# Electric_Scheme.net
KiCad netlist of a schematic drawn in EAGLE
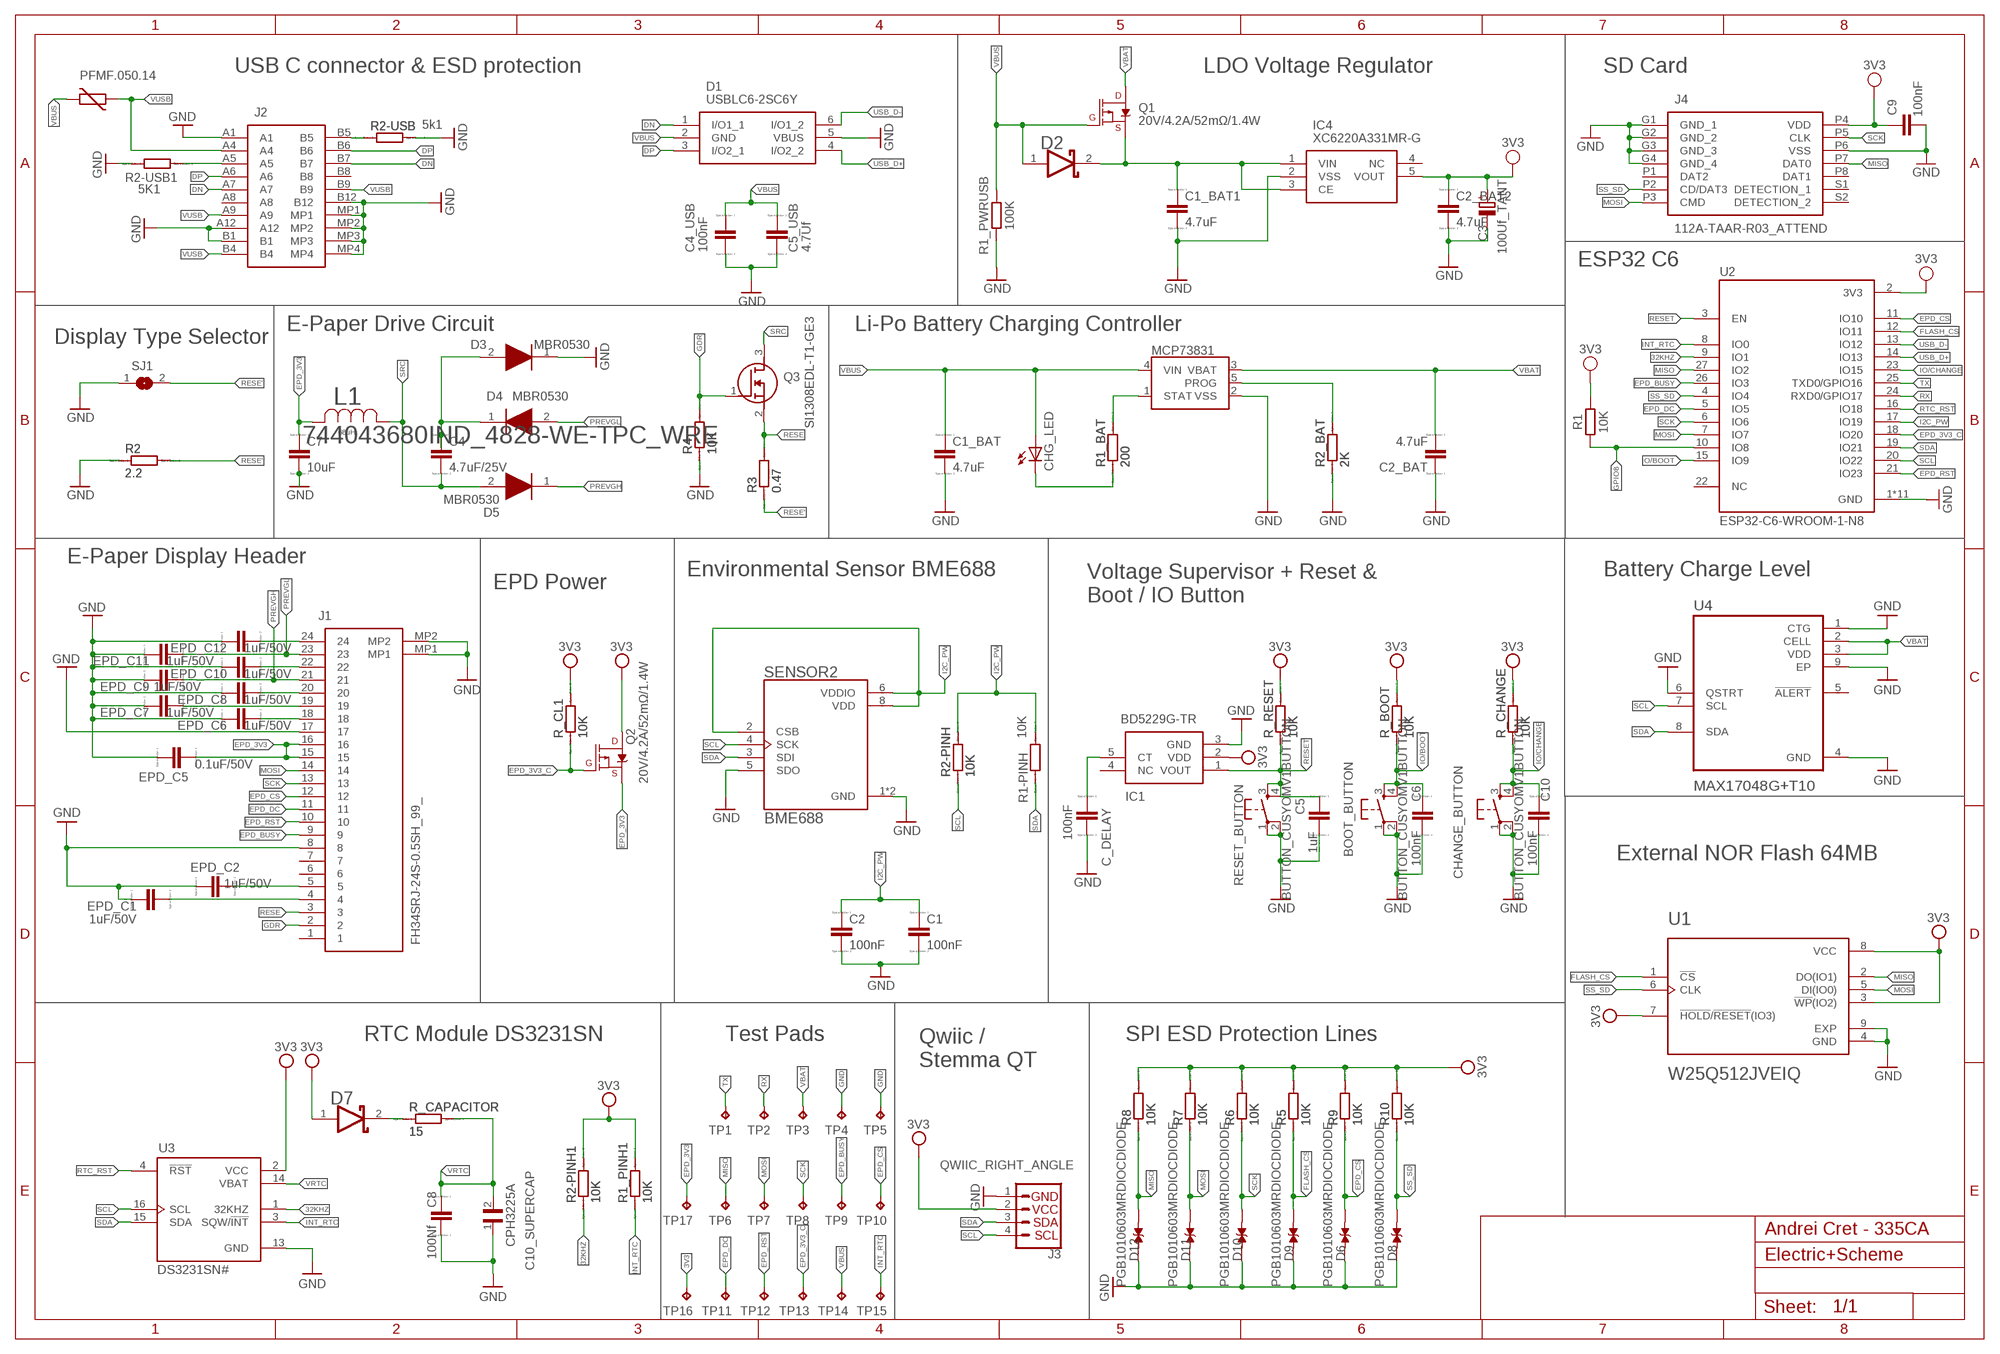
[diagram p0: schematic, sheet 1]

(export (version "E")
  (design (tool "Eeschema 10.0.6"))
  (components
    (comp (ref "BOOT_BUTTON")
      (value "BUTTON_CUSYOMV1BUTTON")
      (footprint "eagle-import:MYBUTTON")
      (libsource (lib "eagle-import") (part "BUTTON_CUSYOMV1BUTTON"))
    )
    (comp (ref "C1")
      (value "100nF")
      (footprint "eagle-import:EAGLE-LTSPICE_C0402")
      (libsource (lib "eagle-import") (part "EAGLE-LTSPICE_C"))
    )
    (comp (ref "C1_BAT")
      (value "4.7uF")
      (footprint "eagle-import:EAGLE-LTSPICE_C0402")
      (libsource (lib "eagle-import") (part "EAGLE-LTSPICE_C"))
    )
    (comp (ref "C1_BAT1")
      (value "4.7uF")
      (footprint "eagle-import:EAGLE-LTSPICE_C0402")
      (libsource (lib "eagle-import") (part "EAGLE-LTSPICE_C"))
    )
    (comp (ref "C2")
      (value "100nF")
      (footprint "eagle-import:EAGLE-LTSPICE_C0402")
      (libsource (lib "eagle-import") (part "EAGLE-LTSPICE_C"))
    )
    (comp (ref "C2_BAT")
      (value "4.7uF")
      (footprint "eagle-import:EAGLE-LTSPICE_C0402")
      (libsource (lib "eagle-import") (part "EAGLE-LTSPICE_C"))
    )
    (comp (ref "C2_BAT2")
      (value "4.7uF")
      (footprint "eagle-import:EAGLE-LTSPICE_C0402")
      (libsource (lib "eagle-import") (part "EAGLE-LTSPICE_C"))
    )
    (comp (ref "C3")
      (value "100Uf_TANT")
      (footprint "eagle-import:CAPMP3216X180N")
      (libsource (lib "eagle-import") (part "CAPACITOR-POLTANTALUM-1206(3216-METRIC)_"))
    )
    (comp (ref "C4")
      (value "4.7uF/25V")
      (footprint "eagle-import:EAGLE-LTSPICE_C0402")
      (libsource (lib "eagle-import") (part "EAGLE-LTSPICE_C"))
    )
    (comp (ref "C4_USB")
      (value "100nF")
      (footprint "eagle-import:EAGLE-LTSPICE_C0402")
      (libsource (lib "eagle-import") (part "EAGLE-LTSPICE_C"))
    )
    (comp (ref "C5")
      (value "1uF")
      (footprint "eagle-import:EAGLE-LTSPICE_C0402")
      (libsource (lib "eagle-import") (part "EAGLE-LTSPICE_C"))
    )
    (comp (ref "C5_USB")
      (value "4.7Uf")
      (footprint "eagle-import:EAGLE-LTSPICE_C0402")
      (libsource (lib "eagle-import") (part "EAGLE-LTSPICE_C"))
    )
    (comp (ref "C6")
      (value "100nF")
      (footprint "eagle-import:EAGLE-LTSPICE_C0402")
      (libsource (lib "eagle-import") (part "EAGLE-LTSPICE_C"))
    )
    (comp (ref "C7")
      (value "10uF")
      (footprint "eagle-import:EAGLE-LTSPICE_C0402")
      (libsource (lib "eagle-import") (part "EAGLE-LTSPICE_C"))
    )
    (comp (ref "C8")
      (value "100Nf")
      (footprint "eagle-import:ESP32_WROVER_EAGLE-LTSPICE_C0402")
      (libsource (lib "eagle-import") (part "ESP32_WROVER_EAGLE-LTSPICE_C"))
    )
    (comp (ref "C9")
      (value "100nF")
      (footprint "eagle-import:CAPC1005X60")
      (libsource (lib "eagle-import") (part "CAPACITORCHIP-0402(1005-METRIC)_"))
    )
    (comp (ref "C10")
      (value "100nF")
      (footprint "eagle-import:EAGLE-LTSPICE_C0402")
      (libsource (lib "eagle-import") (part "EAGLE-LTSPICE_C"))
    )
    (comp (ref "C10_SUPERCAP")
      (value "CPH3225A")
      (footprint "eagle-import:CAPCP3225X100N")
      (fields (field (name "MF") "Seiko Instruments"))
      (libsource (lib "eagle-import") (part "CPH3225A"))
    )
    (comp (ref "CHANGE_BUTTON")
      (value "BUTTON_CUSYOMV1BUTTON")
      (footprint "eagle-import:MYBUTTON")
      (libsource (lib "eagle-import") (part "BUTTON_CUSYOMV1BUTTON"))
    )
    (comp (ref "CHG_LED")
      (value "RED")
      (footprint "eagle-import:ADAFRUIT_CHIP-LED0603")
      (libsource (lib "eagle-import") (part "ADAFRUIT_LEDCHIP-LED0603"))
    )
    (comp (ref "C_DELAY")
      (value "100nF")
      (footprint "eagle-import:EAGLE-LTSPICE_C0402")
      (libsource (lib "eagle-import") (part "EAGLE-LTSPICE_C"))
    )
    (comp (ref "D1")
      (value "USBLC6-2SC6Y")
      (footprint "eagle-import:SOT95P280X145-6N")
      (fields (field (name "MF") "STMicroelectronics"))
      (libsource (lib "eagle-import") (part "USBLC6-2SC6Y"))
    )
    (comp (ref "D2")
      (value "ESP32_WROVER_AVX---SD0805S020S1R0_AVX_SD0805S020S1R0_0_0")
      (footprint "eagle-import:ESP32_WROVER_AVX---SD0805S020S1R0_AVX_SD0805S020S1R0_0")
      (libsource (lib "eagle-import") (part "ESP32_WROVER_AVX---SD0805S020S1R0_AVX_SD0805S020S1R0_0_0"))
    )
    (comp (ref "D3")
      (value "MBR0530")
      (footprint "eagle-import:SOD3716X135N")
      (libsource (lib "eagle-import") (part "MBR0530"))
    )
    (comp (ref "D4")
      (value "MBR0530")
      (footprint "eagle-import:SOD3716X135N")
      (libsource (lib "eagle-import") (part "MBR0530"))
    )
    (comp (ref "D5")
      (value "MBR0530")
      (footprint "eagle-import:SOD3716X135N")
      (libsource (lib "eagle-import") (part "MBR0530"))
    )
    (comp (ref "D6")
      (value "PGB1010603MRDIOCDIODE")
      (footprint "eagle-import:DIOC1608X36N")
      (libsource (lib "eagle-import") (part "PGB1010603MRDIOCDIODE"))
    )
    (comp (ref "D7")
      (value "ESP32_WROVER_AVX---SD0805S020S1R0_AVX_SD0805S020S1R0_0_0")
      (footprint "eagle-import:ESP32_WROVER_AVX---SD0805S020S1R0_AVX_SD0805S020S1R0_0")
      (libsource (lib "eagle-import") (part "ESP32_WROVER_AVX---SD0805S020S1R0_AVX_SD0805S020S1R0_0_0"))
    )
    (comp (ref "D8")
      (value "PGB1010603MRDIOCDIODE")
      (footprint "eagle-import:DIOC1608X36N")
      (libsource (lib "eagle-import") (part "PGB1010603MRDIOCDIODE"))
    )
    (comp (ref "D9")
      (value "PGB1010603MRDIOCDIODE")
      (footprint "eagle-import:DIOC1608X36N")
      (libsource (lib "eagle-import") (part "PGB1010603MRDIOCDIODE"))
    )
    (comp (ref "D10")
      (value "PGB1010603MRDIOCDIODE")
      (footprint "eagle-import:DIOC1608X36N")
      (libsource (lib "eagle-import") (part "PGB1010603MRDIOCDIODE"))
    )
    (comp (ref "D11")
      (value "PGB1010603MRDIOCDIODE")
      (footprint "eagle-import:DIOC1608X36N")
      (libsource (lib "eagle-import") (part "PGB1010603MRDIOCDIODE"))
    )
    (comp (ref "D12")
      (value "PGB1010603MRDIOCDIODE")
      (footprint "eagle-import:DIOC1608X36N")
      (libsource (lib "eagle-import") (part "PGB1010603MRDIOCDIODE"))
    )
    (comp (ref "EPD_C1")
      (value "1uF/50V")
      (footprint "eagle-import:ESP32_WROVER_EAGLE-LTSPICE_C0402")
      (libsource (lib "eagle-import") (part "ESP32_WROVER_EAGLE-LTSPICE_C"))
    )
    (comp (ref "EPD_C2")
      (value "1uF/50V")
      (footprint "eagle-import:ESP32_WROVER_EAGLE-LTSPICE_C0402")
      (libsource (lib "eagle-import") (part "ESP32_WROVER_EAGLE-LTSPICE_C"))
    )
    (comp (ref "EPD_C5")
      (value "0.1uF/50V")
      (footprint "eagle-import:EAGLE-LTSPICE_C0402")
      (libsource (lib "eagle-import") (part "EAGLE-LTSPICE_C"))
    )
    (comp (ref "EPD_C6")
      (value "1uF/50V")
      (footprint "eagle-import:EAGLE-LTSPICE_C0402")
      (libsource (lib "eagle-import") (part "EAGLE-LTSPICE_C"))
    )
    (comp (ref "EPD_C7")
      (value "1uF/50V")
      (footprint "eagle-import:EAGLE-LTSPICE_C0402")
      (libsource (lib "eagle-import") (part "EAGLE-LTSPICE_C"))
    )
    (comp (ref "EPD_C8")
      (value "1uF/50V")
      (footprint "eagle-import:EAGLE-LTSPICE_C0402")
      (libsource (lib "eagle-import") (part "EAGLE-LTSPICE_C"))
    )
    (comp (ref "EPD_C9")
      (value "1uF/50V")
      (footprint "eagle-import:EAGLE-LTSPICE_C0402")
      (libsource (lib "eagle-import") (part "EAGLE-LTSPICE_C"))
    )
    (comp (ref "EPD_C10")
      (value "1uF/50V")
      (footprint "eagle-import:EAGLE-LTSPICE_C0402")
      (libsource (lib "eagle-import") (part "EAGLE-LTSPICE_C"))
    )
    (comp (ref "EPD_C11")
      (value "1uF/50V")
      (footprint "eagle-import:EAGLE-LTSPICE_C0402")
      (libsource (lib "eagle-import") (part "EAGLE-LTSPICE_C"))
    )
    (comp (ref "EPD_C12")
      (value "1uF/50V")
      (footprint "eagle-import:EAGLE-LTSPICE_C0402")
      (libsource (lib "eagle-import") (part "EAGLE-LTSPICE_C"))
    )
    (comp (ref "IC1")
      (value "BD5229G-TR")
      (footprint "eagle-import:SOT95P280X125-5N")
      (fields (field (name "MOUSER_PART_NUMBER") "755-BD5229G-TR"))
      (libsource (lib "eagle-import") (part "BD5229G-TR"))
    )
    (comp (ref "IC4")
      (value "XC6220A331MR-G")
      (footprint "eagle-import:SOT95P280X120-5N")
      (fields (field (name "MOUSER_PART_NUMBER") "865-XC6220A331MR-G"))
      (libsource (lib "eagle-import") (part "XC6220A331MR-G"))
    )
    (comp (ref "J1")
      (value "FH34SRJ-24S-0.5SH_99_")
      (footprint "eagle-import:FH34SRJ24S05SH99")
      (fields
        (field (name "MANUFACTURER_PART_NUMBER") "FH34SRJ-24S-0.5SH(99)")
        (field (name "MOUSER_PART_NUMBER") "798-FH34SRJ24S05SH99")
      )
      (libsource (lib "eagle-import") (part "FH34SRJ-24S-0.5SH_99_"))
    )
    (comp (ref "J2")
      (value "SAMACSYS_PARTS_USB4110-GF-A")
      (footprint "eagle-import:SAMACSYS_PARTS_USB4110GFA")
      (fields
        (field (name "MANUFACTURER_PART_NUMBER") "USB4110-GF-A")
        (field (name "MOUSER_PART_NUMBER") "640-USB4110-GF-A")
      )
      (libsource (lib "eagle-import") (part "SAMACSYS_PARTS_USB4110-GF-A"))
    )
    (comp (ref "J3")
      (value "QWIIC_RIGHT_ANGLE")
      (footprint "eagle-import:JST04_1MM_RA")
      (libsource (lib "eagle-import") (part "QWIIC_CONNECTORJS-1MM"))
    )
    (comp (ref "J4")
      (value "112A-TAAR-R03_ATTEND")
      (footprint "eagle-import:112ATAARR03ATTEND")
      (fields (field (name "MANUFACTURER_PART_NUMBER") "112A-TAAR-R03 ATTEND"))
      (libsource (lib "eagle-import") (part "112A-TAAR-R03_ATTEND"))
    )
    (comp (ref "L1")
      (value "744043680IND_4828-WE-TPC_WRE")
      (footprint "eagle-import:IND_4828-WE-TPC_WRE")
      (fields
        (field (name "MANUFACTURER_PART_NUMBER") "744043680")
        (field (name "ETC") "68uH")
        (field (name "COPYRIGHT") "Copyright (C) 2024 Ultra Librarian. All rights reserved.")
      )
      (libsource (lib "eagle-import") (part "744043680IND_4828-WE-TPC_WRE"))
    )
    (comp (ref "MCP73831")
      (value "ESP32_WROVER_SPARKFUN-IC-POWER_MCP73831")
      (footprint "eagle-import:ESP32_WROVER_SPARKFUN-IC-POWER_SOT23-5")
      (libsource (lib "eagle-import") (part "ESP32_WROVER_SPARKFUN-IC-POWER_MCP73831"))
    )
    (comp (ref "PFMF.050.14")
      (value "ESP32C6_VARISTORCN1812")
      (footprint "eagle-import:ESP32C6_VARISTOR_CT_CN1812")
      (libsource (lib "eagle-import") (part "ESP32C6_VARISTORCN1812"))
    )
    (comp (ref "Q1")
      (value "20V/4.2A/52mΩ/1.4W")
      (footprint "eagle-import:ESP32_WROVER_SPARKFUN-DISCRETESEMI_SOT23-3")
      (libsource (lib "eagle-import") (part "ESP32_WROVER_SPARKFUN-DISCRETESEMI_MOSFET_PCH-DMG2305UX-7"))
    )
    (comp (ref "Q2")
      (value "20V/4.2A/52mΩ/1.4W")
      (footprint "eagle-import:ESP32_WROVER_SPARKFUN-DISCRETESEMI_SOT23-3")
      (libsource (lib "eagle-import") (part "ESP32_WROVER_SPARKFUN-DISCRETESEMI_MOSFET_PCH-DMG2305UX-7"))
    )
    (comp (ref "Q3")
      (value "SI1308EDL-T1-GE3")
      (footprint "eagle-import:SOT65P210X110-3N")
      (fields (field (name "MF") "Vishay Siliconix"))
      (libsource (lib "eagle-import") (part "SI1308EDL-T1-GE3"))
    )
    (comp (ref "R1")
      (value "10K")
      (footprint "eagle-import:RESC1005X40")
      (libsource (lib "eagle-import") (part "RESISTOR_CHIP-0402(1005-METRIC)_"))
    )
    (comp (ref "R1-PINH")
      (value "10K")
      (footprint "eagle-import:ESP32_WROVER_EAGLE-LTSPICE_R0402")
      (libsource (lib "eagle-import") (part "ESP32_WROVER_EAGLE-LTSPICE_R"))
    )
    (comp (ref "R1_BAT")
      (value "200")
      (footprint "eagle-import:ESP32_WROVER_EAGLE-LTSPICE_R0402")
      (libsource (lib "eagle-import") (part "ESP32_WROVER_EAGLE-LTSPICE_R"))
    )
    (comp (ref "R1_PINH1")
      (value "10K")
      (footprint "eagle-import:ESP32_WROVER_EAGLE-LTSPICE_R0402")
      (libsource (lib "eagle-import") (part "ESP32_WROVER_EAGLE-LTSPICE_R"))
    )
    (comp (ref "R1_PWRUSB")
      (value "100K")
      (footprint "eagle-import:RESC1005X40")
      (libsource (lib "eagle-import") (part "RESISTOR_CHIP-0402(1005-METRIC)_"))
    )
    (comp (ref "R2")
      (value "2.2")
      (footprint "eagle-import:ESP32_WROVER_EAGLE-LTSPICE_R0402")
      (libsource (lib "eagle-import") (part "ESP32_WROVER_EAGLE-LTSPICE_R"))
    )
    (comp (ref "R2-PINH")
      (value "10K")
      (footprint "eagle-import:ESP32_WROVER_EAGLE-LTSPICE_R0402")
      (libsource (lib "eagle-import") (part "ESP32_WROVER_EAGLE-LTSPICE_R"))
    )
    (comp (ref "R2-PINH1")
      (value "10K")
      (footprint "eagle-import:ESP32_WROVER_EAGLE-LTSPICE_R0402")
      (libsource (lib "eagle-import") (part "ESP32_WROVER_EAGLE-LTSPICE_R"))
    )
    (comp (ref "R2-USB")
      (value "5k1")
      (footprint "eagle-import:ESP32_WROVER_EAGLE-LTSPICE_R0402")
      (libsource (lib "eagle-import") (part "ESP32_WROVER_EAGLE-LTSPICE_R"))
    )
    (comp (ref "R2-USB1")
      (value "5K1")
      (footprint "eagle-import:ESP32_WROVER_EAGLE-LTSPICE_R0402")
      (libsource (lib "eagle-import") (part "ESP32_WROVER_EAGLE-LTSPICE_R"))
    )
    (comp (ref "R2_BAT")
      (value "2K")
      (footprint "eagle-import:ESP32_WROVER_EAGLE-LTSPICE_R0402")
      (libsource (lib "eagle-import") (part "ESP32_WROVER_EAGLE-LTSPICE_R"))
    )
    (comp (ref "R3")
      (value "0.47")
      (footprint "eagle-import:ESP32_WROVER_EAGLE-LTSPICE_R0402")
      (libsource (lib "eagle-import") (part "ESP32_WROVER_EAGLE-LTSPICE_R"))
    )
    (comp (ref "R4")
      (value "10K")
      (footprint "eagle-import:ESP32_WROVER_EAGLE-LTSPICE_R0402")
      (libsource (lib "eagle-import") (part "ESP32_WROVER_EAGLE-LTSPICE_R"))
    )
    (comp (ref "R5")
      (value "10K")
      (footprint "eagle-import:ESP32_WROVER_EAGLE-LTSPICE_R0402")
      (libsource (lib "eagle-import") (part "ESP32_WROVER_EAGLE-LTSPICE_R"))
    )
    (comp (ref "R6")
      (value "10K")
      (footprint "eagle-import:ESP32_WROVER_EAGLE-LTSPICE_R0402")
      (libsource (lib "eagle-import") (part "ESP32_WROVER_EAGLE-LTSPICE_R"))
    )
    (comp (ref "R7")
      (value "10K")
      (footprint "eagle-import:ESP32_WROVER_EAGLE-LTSPICE_R0402")
      (libsource (lib "eagle-import") (part "ESP32_WROVER_EAGLE-LTSPICE_R"))
    )
    (comp (ref "R8")
      (value "10K")
      (footprint "eagle-import:ESP32_WROVER_EAGLE-LTSPICE_R0402")
      (libsource (lib "eagle-import") (part "ESP32_WROVER_EAGLE-LTSPICE_R"))
    )
    (comp (ref "R9")
      (value "10K")
      (footprint "eagle-import:ESP32_WROVER_EAGLE-LTSPICE_R0402")
      (libsource (lib "eagle-import") (part "ESP32_WROVER_EAGLE-LTSPICE_R"))
    )
    (comp (ref "R10")
      (value "10K")
      (footprint "eagle-import:ESP32_WROVER_EAGLE-LTSPICE_R0402")
      (libsource (lib "eagle-import") (part "ESP32_WROVER_EAGLE-LTSPICE_R"))
    )
    (comp (ref "RESET_BUTTON")
      (value "BUTTON_CUSYOMV1BUTTON")
      (footprint "eagle-import:MYBUTTON")
      (libsource (lib "eagle-import") (part "BUTTON_CUSYOMV1BUTTON"))
    )
    (comp (ref "R_BOOT")
      (value "10K")
      (footprint "eagle-import:ESP32_WROVER_EAGLE-LTSPICE_R0402")
      (libsource (lib "eagle-import") (part "ESP32_WROVER_EAGLE-LTSPICE_R"))
    )
    (comp (ref "R_CAPACITOR")
      (value "15")
      (footprint "eagle-import:ESP32_WROVER_EAGLE-LTSPICE_R0402")
      (libsource (lib "eagle-import") (part "ESP32_WROVER_EAGLE-LTSPICE_R"))
    )
    (comp (ref "R_CHANGE")
      (value "10K")
      (footprint "eagle-import:ESP32_WROVER_EAGLE-LTSPICE_R0402")
      (libsource (lib "eagle-import") (part "ESP32_WROVER_EAGLE-LTSPICE_R"))
    )
    (comp (ref "R_CL1")
      (value "10K")
      (footprint "eagle-import:ESP32_WROVER_EAGLE-LTSPICE_R0402")
      (libsource (lib "eagle-import") (part "ESP32_WROVER_EAGLE-LTSPICE_R"))
    )
    (comp (ref "R_RESET")
      (value "10K")
      (footprint "eagle-import:ESP32_WROVER_EAGLE-LTSPICE_R0402")
      (libsource (lib "eagle-import") (part "ESP32_WROVER_EAGLE-LTSPICE_R"))
    )
    (comp (ref "SENSOR2")
      (value "BME688")
      (footprint "eagle-import:ESP32_WROVER_BME680_PSON80P300X300X100-8N")
      (fields (field (name "MF") "Bosch Sensortec") (field (name "MP") "BME680"))
      (libsource (lib "eagle-import") (part "ESP32_WROVER_BME680_BME680"))
    )
    (comp (ref "SJ1")
      (value "SOLDERJUMPER")
      (footprint "eagle-import:SJ")
      (libsource (lib "eagle-import") (part "SJ"))
    )
    (comp (ref "TP1")
      (value "TP")
      (footprint "eagle-import:TP20R")
      (libsource (lib "eagle-import") (part "TP"))
    )
    (comp (ref "TP2")
      (value "TP")
      (footprint "eagle-import:TP20R")
      (libsource (lib "eagle-import") (part "TP"))
    )
    (comp (ref "TP3")
      (value "TP")
      (footprint "eagle-import:TP20R")
      (libsource (lib "eagle-import") (part "TP"))
    )
    (comp (ref "TP4")
      (value "TP")
      (footprint "eagle-import:TP20R")
      (libsource (lib "eagle-import") (part "TP"))
    )
    (comp (ref "TP5")
      (value "TP")
      (footprint "eagle-import:TP20R")
      (libsource (lib "eagle-import") (part "TP"))
    )
    (comp (ref "TP6")
      (value "TP")
      (footprint "eagle-import:TP20R")
      (libsource (lib "eagle-import") (part "TP"))
    )
    (comp (ref "TP7")
      (value "TP")
      (footprint "eagle-import:TP20R")
      (libsource (lib "eagle-import") (part "TP"))
    )
    (comp (ref "TP8")
      (value "TP")
      (footprint "eagle-import:TP20R")
      (libsource (lib "eagle-import") (part "TP"))
    )
    (comp (ref "TP9")
      (value "TP")
      (footprint "eagle-import:TP20R")
      (libsource (lib "eagle-import") (part "TP"))
    )
    (comp (ref "TP10")
      (value "TP")
      (footprint "eagle-import:TP20R")
      (libsource (lib "eagle-import") (part "TP"))
    )
    (comp (ref "TP11")
      (value "TP")
      (footprint "eagle-import:TP20R")
      (libsource (lib "eagle-import") (part "TP"))
    )
    (comp (ref "TP12")
      (value "TP")
      (footprint "eagle-import:TP20R")
      (libsource (lib "eagle-import") (part "TP"))
    )
    (comp (ref "TP13")
      (value "TP")
      (footprint "eagle-import:TP20R")
      (libsource (lib "eagle-import") (part "TP"))
    )
    (comp (ref "TP14")
      (value "TP")
      (footprint "eagle-import:TP20R")
      (libsource (lib "eagle-import") (part "TP"))
    )
    (comp (ref "TP15")
      (value "TP")
      (footprint "eagle-import:TP20R")
      (libsource (lib "eagle-import") (part "TP"))
    )
    (comp (ref "TP16")
      (value "TP")
      (footprint "eagle-import:TP20R")
      (libsource (lib "eagle-import") (part "TP"))
    )
    (comp (ref "TP17")
      (value "TP")
      (footprint "eagle-import:TP20R")
      (libsource (lib "eagle-import") (part "TP"))
    )
    (comp (ref "U1")
      (value "W25Q512JVEIQ")
      (footprint "eagle-import:SON127P600X800X80-9N")
      (fields (field (name "MF") "Winbond Electronics"))
      (libsource (lib "eagle-import") (part "W25Q512JVEIQ"))
    )
    (comp (ref "U2")
      (value "ESP32-C6-WROOM-1-N8")
      (footprint "eagle-import:XCVR_ESP32-C6-WROOM-1-N8")
      (fields (field (name "MF") "Espressif Systems"))
      (libsource (lib "eagle-import") (part "ESP32-C6-WROOM-1-N8"))
    )
    (comp (ref "U3")
      (value "DS3231SN#")
      (footprint "eagle-import:SOIC127P1032X265-16N")
      (fields (field (name "MF") "Analog Devices"))
      (libsource (lib "eagle-import") (part "DS3231SN#"))
    )
    (comp (ref "U4")
      (value "MAX17048G+T10")
      (footprint "eagle-import:SON50P200X200X80-9N")
      (fields (field (name "MF") "Analog Devices"))
      (libsource (lib "eagle-import") (part "MAX17048G+T10"))
    )
  )
  (nets
    (net (code "1") (name "3V3") (class "Default")
      (node (ref "C2_BAT2") (pin "1") (pinfunction "1_1") (pintype "passive"))
      (node (ref "C3") (pin "1") (pinfunction "+_1") (pintype "passive"))
      (node (ref "C9") (pin "2") (pinfunction "2_2") (pintype "passive"))
      (node (ref "D7") (pin "1") (pinfunction "ANODE_1") (pintype "bidirectional"))
      (node (ref "IC1") (pin "2") (pinfunction "VDD_2") (pintype "bidirectional"))
      (node (ref "IC4") (pin "5") (pinfunction "VOUT_5") (pintype "bidirectional"))
      (node (ref "J3") (pin "2") (pinfunction "2_2") (pintype "power_in"))
      (node (ref "J4") (pin "P4") (pinfunction "VDD_P4") (pintype "bidirectional"))
      (node (ref "Q2") (pin "3") (pinfunction "D_3") (pintype "bidirectional"))
      (node (ref "R1") (pin "2") (pinfunction "2_2") (pintype "passive"))
      (node (ref "R10") (pin "2") (pinfunction "2_2") (pintype "passive"))
      (node (ref "R1_PINH1") (pin "2") (pinfunction "2_2") (pintype "passive"))
      (node (ref "R2-PINH1") (pin "2") (pinfunction "2_2") (pintype "passive"))
      (node (ref "R5") (pin "2") (pinfunction "2_2") (pintype "passive"))
      (node (ref "R6") (pin "2") (pinfunction "2_2") (pintype "passive"))
      (node (ref "R7") (pin "2") (pinfunction "2_2") (pintype "passive"))
      (node (ref "R8") (pin "2") (pinfunction "2_2") (pintype "passive"))
      (node (ref "R9") (pin "2") (pinfunction "2_2") (pintype "passive"))
      (node (ref "R_BOOT") (pin "2") (pinfunction "2_2") (pintype "passive"))
      (node (ref "R_CHANGE") (pin "2") (pinfunction "2_2") (pintype "passive"))
      (node (ref "R_CL1") (pin "2") (pinfunction "2_2") (pintype "passive"))
      (node (ref "R_RESET") (pin "2") (pinfunction "2_2") (pintype "passive"))
      (node (ref "TP16") (pin "TP") (pinfunction "TP_TP") (pintype "input"))
      (node (ref "U1") (pin "3") (pinfunction "~{WP}(IO2)_3") (pintype "bidirectional"))
      (node (ref "U1") (pin "7") (pinfunction "~{HOLD}/~{RESET}(IO3)_7") (pintype "bidirectional"))
      (node (ref "U1") (pin "8") (pinfunction "VCC_8") (pintype "power_in"))
      (node (ref "U2") (pin "2") (pinfunction "3V3_2") (pintype "power_in"))
      (node (ref "U3") (pin "2") (pinfunction "VCC_2") (pintype "power_in"))
    )
    (net (code "2") (name "32KHZ") (class "Default")
      (node (ref "R2-PINH1") (pin "1") (pinfunction "1_1") (pintype "passive"))
      (node (ref "U2") (pin "9") (pinfunction "IO1_9") (pintype "bidirectional"))
      (node (ref "U3") (pin "1") (pinfunction "32KHZ_1") (pintype "output"))
    )
    (net (code "3") (name "DN") (class "Default")
      (node (ref "D1") (pin "1") (pinfunction "I/O1_1_1") (pintype "bidirectional"))
      (node (ref "J2") (pin "A7") (pinfunction "A7_A7") (pintype "bidirectional"))
      (node (ref "J2") (pin "B7") (pinfunction "B7_B7") (pintype "bidirectional"))
    )
    (net (code "4") (name "DP") (class "Default")
      (node (ref "D1") (pin "3") (pinfunction "I/O2_1_3") (pintype "bidirectional"))
      (node (ref "J2") (pin "A6") (pinfunction "A6_A6") (pintype "bidirectional"))
      (node (ref "J2") (pin "B6") (pinfunction "B6_B6") (pintype "bidirectional"))
    )
    (net (code "5") (name "EPD_3V3") (class "Default")
      (node (ref "C7") (pin "1") (pinfunction "1_1") (pintype "passive"))
      (node (ref "EPD_C5") (pin "2") (pinfunction "2_2") (pintype "passive"))
      (node (ref "J1") (pin "15") (pinfunction "15_15") (pintype "bidirectional"))
      (node (ref "J1") (pin "16") (pinfunction "16_16") (pintype "bidirectional"))
      (node (ref "L1") (pin "2") (pinfunction "2_2") (pintype "passive"))
      (node (ref "Q2") (pin "2") (pinfunction "S_2") (pintype "bidirectional"))
      (node (ref "TP17") (pin "TP") (pinfunction "TP_TP") (pintype "input"))
    )
    (net (code "6") (name "EPD_3V3_C") (class "Default")
      (node (ref "Q2") (pin "1") (pinfunction "G_1") (pintype "bidirectional"))
      (node (ref "R_CL1") (pin "1") (pinfunction "1_1") (pintype "passive"))
      (node (ref "TP13") (pin "TP") (pinfunction "TP_TP") (pintype "input"))
      (node (ref "U2") (pin "18") (pinfunction "IO20_18") (pintype "bidirectional"))
    )
    (net (code "7") (name "EPD_BUSY") (class "Default")
      (node (ref "J1") (pin "9") (pinfunction "9_9") (pintype "bidirectional"))
      (node (ref "TP9") (pin "TP") (pinfunction "TP_TP") (pintype "input"))
      (node (ref "U2") (pin "26") (pinfunction "IO3_26") (pintype "bidirectional"))
    )
    (net (code "8") (name "EPD_CS") (class "Default")
      (node (ref "D6") (pin "2") (pinfunction "2_2") (pintype "passive"))
      (node (ref "J1") (pin "12") (pinfunction "12_12") (pintype "bidirectional"))
      (node (ref "R9") (pin "1") (pinfunction "1_1") (pintype "passive"))
      (node (ref "TP10") (pin "TP") (pinfunction "TP_TP") (pintype "input"))
      (node (ref "U2") (pin "11") (pinfunction "IO10_11") (pintype "bidirectional"))
    )
    (net (code "9") (name "EPD_DC") (class "Default")
      (node (ref "J1") (pin "11") (pinfunction "11_11") (pintype "bidirectional"))
      (node (ref "TP11") (pin "TP") (pinfunction "TP_TP") (pintype "input"))
      (node (ref "U2") (pin "5") (pinfunction "IO5_5") (pintype "bidirectional"))
    )
    (net (code "10") (name "EPD_RST") (class "Default")
      (node (ref "J1") (pin "10") (pinfunction "10_10") (pintype "bidirectional"))
      (node (ref "TP12") (pin "TP") (pinfunction "TP_TP") (pintype "input"))
      (node (ref "U2") (pin "21") (pinfunction "IO23_21") (pintype "bidirectional"))
    )
    (net (code "11") (name "FLASH_CS") (class "Default")
      (node (ref "D9") (pin "2") (pinfunction "2_2") (pintype "passive"))
      (node (ref "R5") (pin "1") (pinfunction "1_1") (pintype "passive"))
      (node (ref "U1") (pin "1") (pinfunction "~{CS}_1") (pintype "input"))
      (node (ref "U2") (pin "12") (pinfunction "IO11_12") (pintype "bidirectional"))
    )
    (net (code "12") (name "GDR") (class "Default")
      (node (ref "J1") (pin "2") (pinfunction "2_2") (pintype "bidirectional"))
      (node (ref "Q3") (pin "1") (pinfunction "G_1") (pintype "bidirectional"))
      (node (ref "R4") (pin "2") (pinfunction "2_2") (pintype "passive"))
    )
    (net (code "13") (name "GND") (class "Default")
      (node (ref "BOOT_BUTTON") (pin "1") (pinfunction "1_1") (pintype "passive"))
      (node (ref "BOOT_BUTTON") (pin "2") (pinfunction "2_2") (pintype "passive"))
      (node (ref "C1") (pin "2") (pinfunction "2_2") (pintype "passive"))
      (node (ref "C10") (pin "2") (pinfunction "2_2") (pintype "passive"))
      (node (ref "C10_SUPERCAP") (pin "1") (pinfunction "1_1") (pintype "passive"))
      (node (ref "C1_BAT") (pin "2") (pinfunction "2_2") (pintype "passive"))
      (node (ref "C1_BAT1") (pin "2") (pinfunction "2_2") (pintype "passive"))
      (node (ref "C2") (pin "2") (pinfunction "2_2") (pintype "passive"))
      (node (ref "C2_BAT") (pin "1") (pinfunction "1_1") (pintype "passive"))
      (node (ref "C2_BAT2") (pin "2") (pinfunction "2_2") (pintype "passive"))
      (node (ref "C3") (pin "2") (pinfunction "-_2") (pintype "passive"))
      (node (ref "C4_USB") (pin "2") (pinfunction "2_2") (pintype "passive"))
      (node (ref "C5") (pin "2") (pinfunction "2_2") (pintype "passive"))
      (node (ref "C5_USB") (pin "2") (pinfunction "2_2") (pintype "passive"))
      (node (ref "C6") (pin "2") (pinfunction "2_2") (pintype "passive"))
      (node (ref "C7") (pin "2") (pinfunction "2_2") (pintype "passive"))
      (node (ref "C8") (pin "2") (pinfunction "2_2") (pintype "passive"))
      (node (ref "C9") (pin "1") (pinfunction "1_1") (pintype "passive"))
      (node (ref "CHANGE_BUTTON") (pin "1") (pinfunction "1_1") (pintype "passive"))
      (node (ref "CHANGE_BUTTON") (pin "2") (pinfunction "2_2") (pintype "passive"))
      (node (ref "C_DELAY") (pin "2") (pinfunction "2_2") (pintype "passive"))
      (node (ref "D1") (pin "5") (pinfunction "VBUS_5") (pintype "bidirectional"))
      (node (ref "D10") (pin "1") (pinfunction "1_1") (pintype "passive"))
      (node (ref "D11") (pin "1") (pinfunction "1_1") (pintype "passive"))
      (node (ref "D12") (pin "1") (pinfunction "1_1") (pintype "passive"))
      (node (ref "D3") (pin "1") (pinfunction "K_1") (pintype "bidirectional"))
      (node (ref "D6") (pin "1") (pinfunction "1_1") (pintype "passive"))
      (node (ref "D8") (pin "1") (pinfunction "1_1") (pintype "passive"))
      (node (ref "D9") (pin "1") (pinfunction "1_1") (pintype "passive"))
      (node (ref "EPD_C1") (pin "1") (pinfunction "1_1") (pintype "passive"))
      (node (ref "EPD_C10") (pin "1") (pinfunction "1_1") (pintype "passive"))
      (node (ref "EPD_C11") (pin "1") (pinfunction "1_1") (pintype "passive"))
      (node (ref "EPD_C12") (pin "1") (pinfunction "1_1") (pintype "passive"))
      (node (ref "EPD_C2") (pin "1") (pinfunction "1_1") (pintype "passive"))
      (node (ref "EPD_C5") (pin "1") (pinfunction "1_1") (pintype "passive"))
      (node (ref "EPD_C6") (pin "1") (pinfunction "1_1") (pintype "passive"))
      (node (ref "EPD_C7") (pin "1") (pinfunction "1_1") (pintype "passive"))
      (node (ref "EPD_C8") (pin "1") (pinfunction "1_1") (pintype "passive"))
      (node (ref "EPD_C9") (pin "1") (pinfunction "1_1") (pintype "passive"))
      (node (ref "IC1") (pin "3") (pinfunction "GND_3") (pintype "bidirectional"))
      (node (ref "IC4") (pin "2") (pinfunction "VSS_2") (pintype "bidirectional"))
      (node (ref "J1") (pin "17") (pinfunction "17_17") (pintype "bidirectional"))
      (node (ref "J1") (pin "8") (pinfunction "8_8") (pintype "bidirectional"))
      (node (ref "J1") (pin "MP1") (pinfunction "MP1_MP1") (pintype "bidirectional"))
      (node (ref "J1") (pin "MP2") (pinfunction "MP2_MP2") (pintype "bidirectional"))
      (node (ref "J2") (pin "A1") (pinfunction "A1_A1") (pintype "bidirectional"))
      (node (ref "J2") (pin "A12") (pinfunction "A12_A12") (pintype "bidirectional"))
      (node (ref "J2") (pin "B1") (pinfunction "B1_B1") (pintype "bidirectional"))
      (node (ref "J2") (pin "B12") (pinfunction "B12_B12") (pintype "bidirectional"))
      (node (ref "J2") (pin "MP1") (pinfunction "MP1_MP1") (pintype "bidirectional"))
      (node (ref "J2") (pin "MP2") (pinfunction "MP2_MP2") (pintype "bidirectional"))
      (node (ref "J2") (pin "MP3") (pinfunction "MP3_MP3") (pintype "bidirectional"))
      (node (ref "J2") (pin "MP4") (pinfunction "MP4_MP4") (pintype "bidirectional"))
      (node (ref "J3") (pin "1") (pinfunction "1_1") (pintype "power_in"))
      (node (ref "J4") (pin "G1") (pinfunction "GND_1_G1") (pintype "bidirectional"))
      (node (ref "J4") (pin "G2") (pinfunction "GND_2_G2") (pintype "bidirectional"))
      (node (ref "J4") (pin "G3") (pinfunction "GND_3_G3") (pintype "bidirectional"))
      (node (ref "J4") (pin "G4") (pinfunction "GND_4_G4") (pintype "bidirectional"))
      (node (ref "J4") (pin "P6") (pinfunction "VSS_P6") (pintype "bidirectional"))
      (node (ref "MCP73831") (pin "2") (pinfunction "VSS_2") (pintype "power_in"))
      (node (ref "R1_PWRUSB") (pin "1") (pinfunction "1_1") (pintype "passive"))
      (node (ref "R2") (pin "1") (pinfunction "1_1") (pintype "passive"))
      (node (ref "R2-USB") (pin "2") (pinfunction "2_2") (pintype "passive"))
      (node (ref "R2-USB1") (pin "1") (pinfunction "1_1") (pintype "passive"))
      (node (ref "R2_BAT") (pin "1") (pinfunction "1_1") (pintype "passive"))
      (node (ref "R4") (pin "1") (pinfunction "1_1") (pintype "passive"))
      (node (ref "RESET_BUTTON") (pin "1") (pinfunction "1_1") (pintype "passive"))
      (node (ref "RESET_BUTTON") (pin "2") (pinfunction "2_2") (pintype "passive"))
      (node (ref "SENSOR2") (pin "1") (pinfunction "GND_1") (pintype "power_in"))
      (node (ref "SENSOR2") (pin "5") (pinfunction "SDO_5") (pintype "bidirectional"))
      (node (ref "SENSOR2") (pin "7") (pinfunction "GND_7") (pintype "power_in"))
      (node (ref "SJ1") (pin "1") (pinfunction "1_1") (pintype "passive"))
      (node (ref "TP4") (pin "TP") (pinfunction "TP_TP") (pintype "input"))
      (node (ref "TP5") (pin "TP") (pinfunction "TP_TP") (pintype "input"))
      (node (ref "U1") (pin "4") (pinfunction "GND_4") (pintype "power_in"))
      (node (ref "U1") (pin "9") (pinfunction "EXP_9") (pintype "passive"))
      (node (ref "U2") (pin "1") (pinfunction "GND_1") (pintype "power_in"))
      (node (ref "U2") (pin "28") (pinfunction "GND_28") (pintype "power_in"))
      (node (ref "U2") (pin "29_1") (pinfunction "GND_29_1") (pintype "power_in"))
      (node (ref "U2") (pin "29_2") (pinfunction "GND_29_2") (pintype "power_in"))
      (node (ref "U2") (pin "29_3") (pinfunction "GND_29_3") (pintype "power_in"))
      (node (ref "U2") (pin "29_4") (pinfunction "GND_29_4") (pintype "power_in"))
      (node (ref "U2") (pin "29_5") (pinfunction "GND_29_5") (pintype "power_in"))
      (node (ref "U2") (pin "29_6") (pinfunction "GND_29_6") (pintype "power_in"))
      (node (ref "U2") (pin "29_7") (pinfunction "GND_29_7") (pintype "power_in"))
      (node (ref "U2") (pin "29_8") (pinfunction "GND_29_8") (pintype "power_in"))
      (node (ref "U2") (pin "29_9") (pinfunction "GND_29_9") (pintype "power_in"))
      (node (ref "U3") (pin "13") (pinfunction "GND_13") (pintype "power_in"))
      (node (ref "U4") (pin "1") (pinfunction "CTG_1") (pintype "power_in"))
      (node (ref "U4") (pin "4") (pinfunction "GND_4") (pintype "power_in"))
      (node (ref "U4") (pin "6") (pinfunction "QSTRT_6") (pintype "input"))
      (node (ref "U4") (pin "9") (pinfunction "EP_9") (pintype "power_in"))
    )
    (net (code "14") (name "GPIO8") (class "Default")
      (node (ref "R1") (pin "1") (pinfunction "1_1") (pintype "passive"))
      (node (ref "U2") (pin "10") (pinfunction "IO8_10") (pintype "bidirectional"))
    )
    (net (code "15") (name "I2C_PW") (class "Default")
      (node (ref "C1") (pin "1") (pinfunction "1_1") (pintype "passive"))
      (node (ref "C2") (pin "1") (pinfunction "1_1") (pintype "passive"))
      (node (ref "R1-PINH") (pin "2") (pinfunction "2_2") (pintype "passive"))
      (node (ref "R2-PINH") (pin "2") (pinfunction "2_2") (pintype "passive"))
      (node (ref "SENSOR2") (pin "2") (pinfunction "CSB_2") (pintype "input"))
      (node (ref "SENSOR2") (pin "6") (pinfunction "VDDIO_6") (pintype "power_in"))
      (node (ref "SENSOR2") (pin "8") (pinfunction "VDD_8") (pintype "power_in"))
      (node (ref "U2") (pin "17") (pinfunction "IO19_17") (pintype "bidirectional"))
    )
    (net (code "16") (name "INT_RTC") (class "Default")
      (node (ref "R1_PINH1") (pin "1") (pinfunction "1_1") (pintype "passive"))
      (node (ref "TP15") (pin "TP") (pinfunction "TP_TP") (pintype "input"))
      (node (ref "U2") (pin "8") (pinfunction "IO0_8") (pintype "bidirectional"))
      (node (ref "U3") (pin "3") (pinfunction "SQW/~{INT}_3") (pintype "output"))
    )
    (net (code "17") (name "IO{slash}BOOT") (class "Default")
      (node (ref "BOOT_BUTTON") (pin "3") (pinfunction "3_3") (pintype "passive"))
      (node (ref "BOOT_BUTTON") (pin "4") (pinfunction "4_4") (pintype "passive"))
      (node (ref "C6") (pin "1") (pinfunction "1_1") (pintype "passive"))
      (node (ref "R_BOOT") (pin "1") (pinfunction "1_1") (pintype "passive"))
      (node (ref "U2") (pin "15") (pinfunction "IO9_15") (pintype "bidirectional"))
    )
    (net (code "18") (name "IO{slash}CHANGE") (class "Default")
      (node (ref "C10") (pin "1") (pinfunction "1_1") (pintype "passive"))
      (node (ref "CHANGE_BUTTON") (pin "3") (pinfunction "3_3") (pintype "passive"))
      (node (ref "CHANGE_BUTTON") (pin "4") (pinfunction "4_4") (pintype "passive"))
      (node (ref "R_CHANGE") (pin "1") (pinfunction "1_1") (pintype "passive"))
      (node (ref "U2") (pin "23") (pinfunction "IO15_23") (pintype "bidirectional"))
    )
    (net (code "19") (name "MISO") (class "Default")
      (node (ref "D12") (pin "2") (pinfunction "2_2") (pintype "passive"))
      (node (ref "J4") (pin "P7") (pinfunction "DAT0_P7") (pintype "bidirectional"))
      (node (ref "R8") (pin "1") (pinfunction "1_1") (pintype "passive"))
      (node (ref "TP6") (pin "TP") (pinfunction "TP_TP") (pintype "input"))
      (node (ref "U1") (pin "2") (pinfunction "DO(IO1)_2") (pintype "bidirectional"))
      (node (ref "U2") (pin "27") (pinfunction "IO2_27") (pintype "bidirectional"))
    )
    (net (code "20") (name "MOSI") (class "Default")
      (node (ref "D11") (pin "2") (pinfunction "2_2") (pintype "passive"))
      (node (ref "J1") (pin "14") (pinfunction "14_14") (pintype "bidirectional"))
      (node (ref "J4") (pin "P3") (pinfunction "CMD_P3") (pintype "bidirectional"))
      (node (ref "R7") (pin "1") (pinfunction "1_1") (pintype "passive"))
      (node (ref "TP7") (pin "TP") (pinfunction "TP_TP") (pintype "input"))
      (node (ref "U1") (pin "5") (pinfunction "DI(IO0)_5") (pintype "bidirectional"))
      (node (ref "U2") (pin "7") (pinfunction "IO7_7") (pintype "bidirectional"))
    )
    (net (code "21") (name "Net-(CHG_LED-PadC)") (class "Default")
      (node (ref "CHG_LED") (pin "C") (pinfunction "C_C") (pintype "passive"))
      (node (ref "R1_BAT") (pin "1") (pinfunction "1_1") (pintype "passive"))
    )
    (net (code "22") (name "Net-(D2-CATHODE)") (class "Default")
      (node (ref "C1_BAT1") (pin "1") (pinfunction "1_1") (pintype "passive"))
      (node (ref "D2") (pin "2") (pinfunction "CATHODE_2") (pintype "bidirectional"))
      (node (ref "IC4") (pin "1") (pinfunction "VIN_1") (pintype "bidirectional"))
      (node (ref "IC4") (pin "3") (pinfunction "CE_3") (pintype "bidirectional"))
      (node (ref "Q1") (pin "2") (pinfunction "S_2") (pintype "bidirectional"))
    )
    (net (code "23") (name "Net-(D3-A)") (class "Default")
      (node (ref "C4") (pin "1") (pinfunction "1_1") (pintype "passive"))
      (node (ref "D3") (pin "2") (pinfunction "A_2") (pintype "bidirectional"))
      (node (ref "D4") (pin "1") (pinfunction "K_1") (pintype "bidirectional"))
    )
    (net (code "24") (name "Net-(D7-CATHODE)") (class "Default")
      (node (ref "D7") (pin "2") (pinfunction "CATHODE_2") (pintype "bidirectional"))
      (node (ref "R_CAPACITOR") (pin "1") (pinfunction "1_1") (pintype "passive"))
    )
    (net (code "25") (name "Net-(D8-Pad2)") (class "Default")
      (node (ref "D8") (pin "2") (pinfunction "2_2") (pintype "passive"))
      (node (ref "R10") (pin "1") (pinfunction "1_1") (pintype "passive"))
    )
    (net (code "26") (name "Net-(EPD_C1-Pad2)") (class "Default")
      (node (ref "EPD_C1") (pin "2") (pinfunction "2_2") (pintype "passive"))
      (node (ref "J1") (pin "4") (pinfunction "4_4") (pintype "bidirectional"))
    )
    (net (code "27") (name "Net-(EPD_C2-Pad2)") (class "Default")
      (node (ref "EPD_C2") (pin "2") (pinfunction "2_2") (pintype "passive"))
      (node (ref "J1") (pin "5") (pinfunction "5_5") (pintype "bidirectional"))
    )
    (net (code "28") (name "Net-(EPD_C6-Pad2)") (class "Default")
      (node (ref "EPD_C6") (pin "2") (pinfunction "2_2") (pintype "passive"))
      (node (ref "J1") (pin "18") (pinfunction "18_18") (pintype "bidirectional"))
    )
    (net (code "29") (name "Net-(EPD_C7-Pad2)") (class "Default")
      (node (ref "EPD_C7") (pin "2") (pinfunction "2_2") (pintype "passive"))
      (node (ref "J1") (pin "19") (pinfunction "19_19") (pintype "bidirectional"))
    )
    (net (code "30") (name "Net-(EPD_C8-Pad2)") (class "Default")
      (node (ref "EPD_C8") (pin "2") (pinfunction "2_2") (pintype "passive"))
      (node (ref "J1") (pin "20") (pinfunction "20_20") (pintype "bidirectional"))
    )
    (net (code "31") (name "Net-(EPD_C10-Pad2)") (class "Default")
      (node (ref "EPD_C10") (pin "2") (pinfunction "2_2") (pintype "passive"))
      (node (ref "J1") (pin "22") (pinfunction "22_22") (pintype "bidirectional"))
    )
    (net (code "32") (name "Net-(EPD_C12-Pad2)") (class "Default")
      (node (ref "EPD_C12") (pin "2") (pinfunction "2_2") (pintype "passive"))
      (node (ref "J1") (pin "24") (pinfunction "24_24") (pintype "bidirectional"))
    )
    (net (code "33") (name "Net-(IC1-CT)") (class "Default")
      (node (ref "C_DELAY") (pin "1") (pinfunction "1_1") (pintype "passive"))
      (node (ref "IC1") (pin "5") (pinfunction "CT_5") (pintype "bidirectional"))
    )
    (net (code "34") (name "Net-(J2-PadA5)") (class "Default")
      (node (ref "J2") (pin "A5") (pinfunction "A5_A5") (pintype "bidirectional"))
      (node (ref "R2-USB1") (pin "2") (pinfunction "2_2") (pintype "passive"))
    )
    (net (code "35") (name "Net-(J2-PadB5)") (class "Default")
      (node (ref "J2") (pin "B5") (pinfunction "B5_B5") (pintype "bidirectional"))
      (node (ref "R2-USB") (pin "1") (pinfunction "1_1") (pintype "passive"))
    )
    (net (code "36") (name "Net-(MCP73831-PROG)") (class "Default")
      (node (ref "MCP73831") (pin "5") (pinfunction "PROG_5") (pintype "input"))
      (node (ref "R2_BAT") (pin "2") (pinfunction "2_2") (pintype "passive"))
    )
    (net (code "37") (name "Net-(MCP73831-STAT)") (class "Default")
      (node (ref "MCP73831") (pin "1") (pinfunction "STAT_1") (pintype "output"))
      (node (ref "R1_BAT") (pin "2") (pinfunction "2_2") (pintype "passive"))
    )
    (net (code "38") (name "PREVGH") (class "Default")
      (node (ref "D5") (pin "1") (pinfunction "K_1") (pintype "bidirectional"))
      (node (ref "EPD_C9") (pin "2") (pinfunction "2_2") (pintype "passive"))
      (node (ref "J1") (pin "21") (pinfunction "21_21") (pintype "bidirectional"))
    )
    (net (code "39") (name "PREVGL") (class "Default")
      (node (ref "D4") (pin "2") (pinfunction "A_2") (pintype "bidirectional"))
      (node (ref "EPD_C11") (pin "2") (pinfunction "2_2") (pintype "passive"))
      (node (ref "J1") (pin "23") (pinfunction "23_23") (pintype "bidirectional"))
    )
    (net (code "40") (name "RESE") (class "Default")
      (node (ref "J1") (pin "3") (pinfunction "3_3") (pintype "bidirectional"))
      (node (ref "Q3") (pin "2") (pinfunction "S_2") (pintype "bidirectional"))
      (node (ref "R3") (pin "2") (pinfunction "2_2") (pintype "passive"))
    )
    (net (code "41") (name "RESE'") (class "Default")
      (node (ref "R2") (pin "2") (pinfunction "2_2") (pintype "passive"))
      (node (ref "R3") (pin "1") (pinfunction "1_1") (pintype "passive"))
      (node (ref "SJ1") (pin "2") (pinfunction "2_2") (pintype "passive"))
    )
    (net (code "42") (name "RESET") (class "Default")
      (node (ref "C5") (pin "1") (pinfunction "1_1") (pintype "passive"))
      (node (ref "IC1") (pin "1") (pinfunction "VOUT_1") (pintype "bidirectional"))
      (node (ref "RESET_BUTTON") (pin "3") (pinfunction "3_3") (pintype "passive"))
      (node (ref "RESET_BUTTON") (pin "4") (pinfunction "4_4") (pintype "passive"))
      (node (ref "R_RESET") (pin "1") (pinfunction "1_1") (pintype "passive"))
      (node (ref "U2") (pin "3") (pinfunction "EN_3") (pintype "input"))
    )
    (net (code "43") (name "RTC_RST") (class "Default")
      (node (ref "U2") (pin "16") (pinfunction "IO18_16") (pintype "bidirectional"))
      (node (ref "U3") (pin "4") (pinfunction "~{RST}_4") (pintype "input"))
    )
    (net (code "44") (name "RX") (class "Default")
      (node (ref "TP2") (pin "TP") (pinfunction "TP_TP") (pintype "input"))
      (node (ref "U2") (pin "24") (pinfunction "RXD0/GPIO17_24") (pintype "bidirectional"))
    )
    (net (code "45") (name "SCK") (class "Default")
      (node (ref "D10") (pin "2") (pinfunction "2_2") (pintype "passive"))
      (node (ref "J1") (pin "13") (pinfunction "13_13") (pintype "bidirectional"))
      (node (ref "J4") (pin "P5") (pinfunction "CLK_P5") (pintype "bidirectional"))
      (node (ref "R6") (pin "1") (pinfunction "1_1") (pintype "passive"))
      (node (ref "TP8") (pin "TP") (pinfunction "TP_TP") (pintype "input"))
      (node (ref "U2") (pin "6") (pinfunction "IO6_6") (pintype "bidirectional"))
    )
    (net (code "46") (name "SCL") (class "Default")
      (node (ref "J3") (pin "4") (pinfunction "4_4") (pintype "passive"))
      (node (ref "R2-PINH") (pin "1") (pinfunction "1_1") (pintype "passive"))
      (node (ref "SENSOR2") (pin "4") (pinfunction "SCK_4") (pintype "input"))
      (node (ref "U2") (pin "20") (pinfunction "IO22_20") (pintype "bidirectional"))
      (node (ref "U3") (pin "16") (pinfunction "SCL_16") (pintype "input"))
      (node (ref "U4") (pin "7") (pinfunction "SCL_7") (pintype "input"))
    )
    (net (code "47") (name "SDA") (class "Default")
      (node (ref "J3") (pin "3") (pinfunction "3_3") (pintype "passive"))
      (node (ref "R1-PINH") (pin "1") (pinfunction "1_1") (pintype "passive"))
      (node (ref "SENSOR2") (pin "3") (pinfunction "SDI_3") (pintype "bidirectional"))
      (node (ref "U2") (pin "19") (pinfunction "IO21_19") (pintype "bidirectional"))
      (node (ref "U3") (pin "15") (pinfunction "SDA_15") (pintype "bidirectional"))
      (node (ref "U4") (pin "8") (pinfunction "SDA_8") (pintype "bidirectional"))
    )
    (net (code "48") (name "SRC") (class "Default")
      (node (ref "C4") (pin "2") (pinfunction "2_2") (pintype "passive"))
      (node (ref "D5") (pin "2") (pinfunction "A_2") (pintype "bidirectional"))
      (node (ref "L1") (pin "1") (pinfunction "1_1") (pintype "passive"))
      (node (ref "Q3") (pin "3") (pinfunction "D_3") (pintype "bidirectional"))
    )
    (net (code "49") (name "SS_SD") (class "Default")
      (node (ref "J4") (pin "P2") (pinfunction "CD/DAT3_P2") (pintype "bidirectional"))
      (node (ref "U1") (pin "6") (pinfunction "CLK_6") (pintype "input"))
      (node (ref "U2") (pin "4") (pinfunction "IO4_4") (pintype "bidirectional"))
    )
    (net (code "50") (name "TX") (class "Default")
      (node (ref "TP1") (pin "TP") (pinfunction "TP_TP") (pintype "input"))
      (node (ref "U2") (pin "25") (pinfunction "TXD0/GPIO16_25") (pintype "bidirectional"))
    )
    (net (code "51") (name "USB_D+") (class "Default")
      (node (ref "D1") (pin "4") (pinfunction "I/O2_2_4") (pintype "bidirectional"))
      (node (ref "U2") (pin "14") (pinfunction "IO13_14") (pintype "bidirectional"))
    )
    (net (code "52") (name "USB_D-") (class "Default")
      (node (ref "D1") (pin "6") (pinfunction "I/O1_2_6") (pintype "bidirectional"))
      (node (ref "U2") (pin "13") (pinfunction "IO12_13") (pintype "bidirectional"))
    )
    (net (code "53") (name "VBAT") (class "Default")
      (node (ref "C2_BAT") (pin "2") (pinfunction "2_2") (pintype "passive"))
      (node (ref "MCP73831") (pin "3") (pinfunction "VBAT_3") (pintype "power_in"))
      (node (ref "Q1") (pin "3") (pinfunction "D_3") (pintype "bidirectional"))
      (node (ref "TP3") (pin "TP") (pinfunction "TP_TP") (pintype "input"))
      (node (ref "U4") (pin "2") (pinfunction "CELL_2") (pintype "power_in"))
      (node (ref "U4") (pin "3") (pinfunction "VDD_3") (pintype "power_in"))
    )
    (net (code "54") (name "VBUS") (class "Default")
      (node (ref "C1_BAT") (pin "1") (pinfunction "1_1") (pintype "passive"))
      (node (ref "C4_USB") (pin "1") (pinfunction "1_1") (pintype "passive"))
      (node (ref "C5_USB") (pin "1") (pinfunction "1_1") (pintype "passive"))
      (node (ref "CHG_LED") (pin "A") (pinfunction "A_A") (pintype "passive"))
      (node (ref "D1") (pin "2") (pinfunction "GND_2") (pintype "bidirectional"))
      (node (ref "D2") (pin "1") (pinfunction "ANODE_1") (pintype "bidirectional"))
      (node (ref "MCP73831") (pin "4") (pinfunction "VIN_4") (pintype "power_in"))
      (node (ref "PFMF.050.14") (pin "2") (pinfunction "2_2") (pintype "passive"))
      (node (ref "Q1") (pin "1") (pinfunction "G_1") (pintype "bidirectional"))
      (node (ref "R1_PWRUSB") (pin "2") (pinfunction "2_2") (pintype "passive"))
      (node (ref "TP14") (pin "TP") (pinfunction "TP_TP") (pintype "input"))
    )
    (net (code "55") (name "VRTC") (class "Default")
      (node (ref "C10_SUPERCAP") (pin "2") (pinfunction "2_2") (pintype "passive"))
      (node (ref "C8") (pin "1") (pinfunction "1_1") (pintype "passive"))
      (node (ref "R_CAPACITOR") (pin "2") (pinfunction "2_2") (pintype "passive"))
      (node (ref "U3") (pin "14") (pinfunction "VBAT_14") (pintype "power_in"))
    )
    (net (code "56") (name "VUSB") (class "Default")
      (node (ref "J2") (pin "A4") (pinfunction "A4_A4") (pintype "bidirectional"))
      (node (ref "J2") (pin "A9") (pinfunction "A9_A9") (pintype "bidirectional"))
      (node (ref "J2") (pin "B4") (pinfunction "B4_B4") (pintype "bidirectional"))
      (node (ref "J2") (pin "B9") (pinfunction "B9_B9") (pintype "bidirectional"))
      (node (ref "PFMF.050.14") (pin "1") (pinfunction "1_1") (pintype "passive"))
    )
    (net (code "57") (name "unconnected-(IC1-NC-Pad4)") (class "Default")
      (node (ref "IC1") (pin "4") (pinfunction "NC_4") (pintype "no_connect"))
    )
    (net (code "58") (name "unconnected-(IC4-NC-Pad4)") (class "Default")
      (node (ref "IC4") (pin "4") (pinfunction "NC_4") (pintype "no_connect"))
    )
    (net (code "59") (name "unconnected-(J1-Pad1)") (class "Default")
      (node (ref "J1") (pin "1") (pinfunction "1_1") (pintype "bidirectional"))
    )
    (net (code "60") (name "unconnected-(J1-Pad6)") (class "Default")
      (node (ref "J1") (pin "6") (pinfunction "6_6") (pintype "bidirectional"))
    )
    (net (code "61") (name "unconnected-(J1-Pad7)") (class "Default")
      (node (ref "J1") (pin "7") (pinfunction "7_7") (pintype "bidirectional"))
    )
    (net (code "62") (name "unconnected-(J2-PadA8)") (class "Default")
      (node (ref "J2") (pin "A8") (pinfunction "A8_A8") (pintype "bidirectional"))
    )
    (net (code "63") (name "unconnected-(J2-PadB8)") (class "Default")
      (node (ref "J2") (pin "B8") (pinfunction "B8_B8") (pintype "bidirectional"))
    )
    (net (code "64") (name "unconnected-(J4-DAT1-PadP8)") (class "Default")
      (node (ref "J4") (pin "P8") (pinfunction "DAT1_P8") (pintype "bidirectional"))
    )
    (net (code "65") (name "unconnected-(J4-DAT2-PadP1)") (class "Default")
      (node (ref "J4") (pin "P1") (pinfunction "DAT2_P1") (pintype "bidirectional"))
    )
    (net (code "66") (name "unconnected-(J4-DETECTION_1-PadS1)") (class "Default")
      (node (ref "J4") (pin "S1") (pinfunction "DETECTION_1_S1") (pintype "bidirectional"))
    )
    (net (code "67") (name "unconnected-(J4-DETECTION_2-PadS2)") (class "Default")
      (node (ref "J4") (pin "S2") (pinfunction "DETECTION_2_S2") (pintype "bidirectional"))
    )
    (net (code "68") (name "unconnected-(U2-NC-Pad22)") (class "Default")
      (node (ref "U2") (pin "22") (pinfunction "NC_22") (pintype "no_connect"))
    )
    (net (code "69") (name "unconnected-(U4-~{ALERT}-Pad5)") (class "Default")
      (node (ref "U4") (pin "5") (pinfunction "~{ALERT}_5") (pintype "output"))
    )
  )
)
